# VFD_alpha_Sheet3.net
KiCad netlist of a schematic drawn in Altium Designer
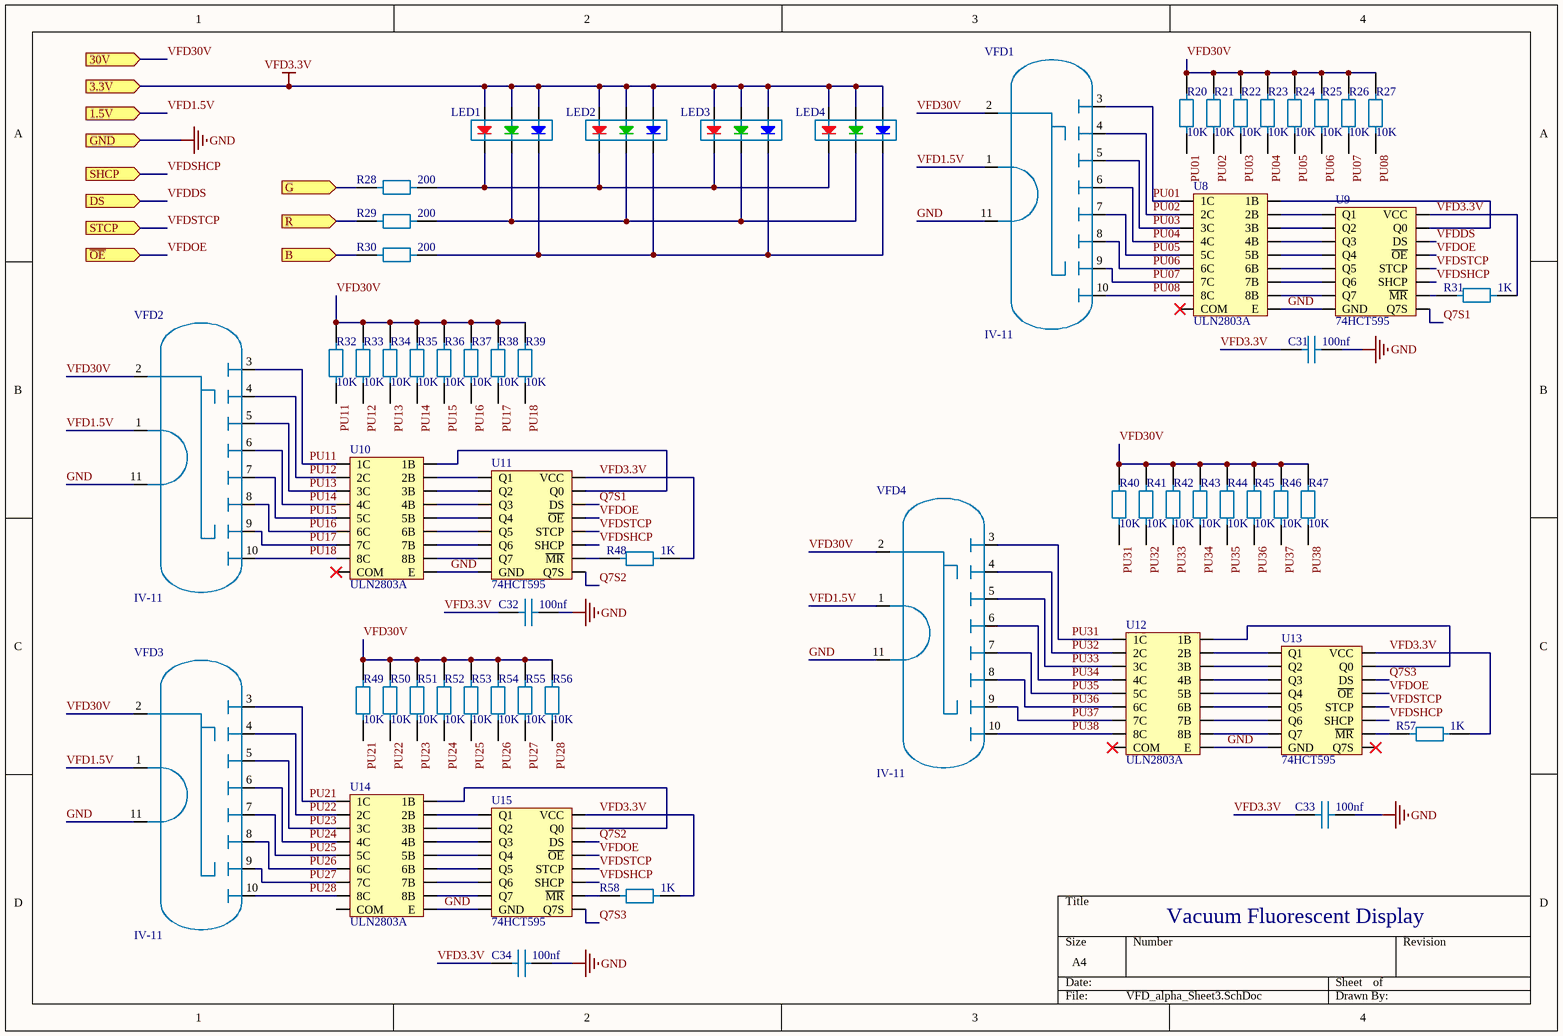
[diagram p0: VFD_alpha_Sheet3.SchDoc]

(export (version "E")
  (design (tool "Eeschema 10.0.6"))
  (components
    (comp (ref "C31")
      (value "100nf")
      (footprint "0603")
      (fields (field (name "Comment") "C"))
      (libsource (lib "ZZB_Lib") (part "C(0603)"))
    )
    (comp (ref "C32")
      (value "100nf")
      (footprint "0603")
      (fields (field (name "Comment") "C"))
      (libsource (lib "ZZB_Lib") (part "C(0603)"))
    )
    (comp (ref "C33")
      (value "100nf")
      (footprint "0603")
      (fields (field (name "Comment") "C"))
      (libsource (lib "ZZB_Lib") (part "C(0603)"))
    )
    (comp (ref "C34")
      (value "100nf")
      (footprint "0603")
      (fields (field (name "Comment") "C"))
      (libsource (lib "ZZB_Lib") (part "C(0603)"))
    )
    (comp (ref "LED1") (value "RGBLED") (footprint "RGBLED") (libsource (lib "ZZB_Lib") (part "RGBLED")))
    (comp (ref "LED2") (value "RGBLED") (footprint "RGBLED") (libsource (lib "ZZB_Lib") (part "RGBLED")))
    (comp (ref "LED3") (value "RGBLED") (footprint "RGBLED") (libsource (lib "ZZB_Lib") (part "RGBLED")))
    (comp (ref "LED4") (value "RGBLED") (footprint "RGBLED") (libsource (lib "ZZB_Lib") (part "RGBLED")))
    (comp (ref "R20")
      (value "10K")
      (footprint "R-1/4W")
      (fields (field (name "Comment") "R(1/4W)"))
      (libsource (lib "ZZB_Lib") (part "R(1/4W)"))
    )
    (comp (ref "R21")
      (value "10K")
      (footprint "R-1/4W")
      (fields (field (name "Comment") "R(1/4W)"))
      (libsource (lib "ZZB_Lib") (part "R(1/4W)"))
    )
    (comp (ref "R22")
      (value "10K")
      (footprint "R-1/4W")
      (fields (field (name "Comment") "R(1/4W)"))
      (libsource (lib "ZZB_Lib") (part "R(1/4W)"))
    )
    (comp (ref "R23")
      (value "10K")
      (footprint "R-1/4W")
      (fields (field (name "Comment") "R(1/4W)"))
      (libsource (lib "ZZB_Lib") (part "R(1/4W)"))
    )
    (comp (ref "R24")
      (value "10K")
      (footprint "R-1/4W")
      (fields (field (name "Comment") "R(1/4W)"))
      (libsource (lib "ZZB_Lib") (part "R(1/4W)"))
    )
    (comp (ref "R25")
      (value "10K")
      (footprint "R-1/4W")
      (fields (field (name "Comment") "R(1/4W)"))
      (libsource (lib "ZZB_Lib") (part "R(1/4W)"))
    )
    (comp (ref "R26")
      (value "10K")
      (footprint "R-1/4W")
      (fields (field (name "Comment") "R(1/4W)"))
      (libsource (lib "ZZB_Lib") (part "R(1/4W)"))
    )
    (comp (ref "R27")
      (value "10K")
      (footprint "R-1/4W")
      (fields (field (name "Comment") "R(1/4W)"))
      (libsource (lib "ZZB_Lib") (part "R(1/4W)"))
    )
    (comp (ref "R28")
      (value "200")
      (footprint "0603")
      (fields (field (name "Comment") "R"))
      (libsource (lib "ZZB_Lib") (part "R(0603)"))
    )
    (comp (ref "R29")
      (value "200")
      (footprint "0603")
      (fields (field (name "Comment") "R"))
      (libsource (lib "ZZB_Lib") (part "R(0603)"))
    )
    (comp (ref "R30")
      (value "200")
      (footprint "0603")
      (fields (field (name "Comment") "R"))
      (libsource (lib "ZZB_Lib") (part "R(0603)"))
    )
    (comp (ref "R31")
      (value "1K")
      (footprint "0603")
      (fields (field (name "Comment") "R"))
      (libsource (lib "ZZB_Lib") (part "R(0603)"))
    )
    (comp (ref "R32")
      (value "10K")
      (footprint "R-1/4W")
      (fields (field (name "Comment") "R(1/4W)"))
      (libsource (lib "ZZB_Lib") (part "R(1/4W)"))
    )
    (comp (ref "R33")
      (value "10K")
      (footprint "R-1/4W")
      (fields (field (name "Comment") "R(1/4W)"))
      (libsource (lib "ZZB_Lib") (part "R(1/4W)"))
    )
    (comp (ref "R34")
      (value "10K")
      (footprint "R-1/4W")
      (fields (field (name "Comment") "R(1/4W)"))
      (libsource (lib "ZZB_Lib") (part "R(1/4W)"))
    )
    (comp (ref "R35")
      (value "10K")
      (footprint "R-1/4W")
      (fields (field (name "Comment") "R(1/4W)"))
      (libsource (lib "ZZB_Lib") (part "R(1/4W)"))
    )
    (comp (ref "R36")
      (value "10K")
      (footprint "R-1/4W")
      (fields (field (name "Comment") "R(1/4W)"))
      (libsource (lib "ZZB_Lib") (part "R(1/4W)"))
    )
    (comp (ref "R37")
      (value "10K")
      (footprint "R-1/4W")
      (fields (field (name "Comment") "R(1/4W)"))
      (libsource (lib "ZZB_Lib") (part "R(1/4W)"))
    )
    (comp (ref "R38")
      (value "10K")
      (footprint "R-1/4W")
      (fields (field (name "Comment") "R(1/4W)"))
      (libsource (lib "ZZB_Lib") (part "R(1/4W)"))
    )
    (comp (ref "R39")
      (value "10K")
      (footprint "R-1/4W")
      (fields (field (name "Comment") "R(1/4W)"))
      (libsource (lib "ZZB_Lib") (part "R(1/4W)"))
    )
    (comp (ref "R40")
      (value "10K")
      (footprint "R-1/4W")
      (fields (field (name "Comment") "R(1/4W)"))
      (libsource (lib "ZZB_Lib") (part "R(1/4W)"))
    )
    (comp (ref "R41")
      (value "10K")
      (footprint "R-1/4W")
      (fields (field (name "Comment") "R(1/4W)"))
      (libsource (lib "ZZB_Lib") (part "R(1/4W)"))
    )
    (comp (ref "R42")
      (value "10K")
      (footprint "R-1/4W")
      (fields (field (name "Comment") "R(1/4W)"))
      (libsource (lib "ZZB_Lib") (part "R(1/4W)"))
    )
    (comp (ref "R43")
      (value "10K")
      (footprint "R-1/4W")
      (fields (field (name "Comment") "R(1/4W)"))
      (libsource (lib "ZZB_Lib") (part "R(1/4W)"))
    )
    (comp (ref "R44")
      (value "10K")
      (footprint "R-1/4W")
      (fields (field (name "Comment") "R(1/4W)"))
      (libsource (lib "ZZB_Lib") (part "R(1/4W)"))
    )
    (comp (ref "R45")
      (value "10K")
      (footprint "R-1/4W")
      (fields (field (name "Comment") "R(1/4W)"))
      (libsource (lib "ZZB_Lib") (part "R(1/4W)"))
    )
    (comp (ref "R46")
      (value "10K")
      (footprint "R-1/4W")
      (fields (field (name "Comment") "R(1/4W)"))
      (libsource (lib "ZZB_Lib") (part "R(1/4W)"))
    )
    (comp (ref "R47")
      (value "10K")
      (footprint "R-1/4W")
      (fields (field (name "Comment") "R(1/4W)"))
      (libsource (lib "ZZB_Lib") (part "R(1/4W)"))
    )
    (comp (ref "R48")
      (value "1K")
      (footprint "0603")
      (fields (field (name "Comment") "R"))
      (libsource (lib "ZZB_Lib") (part "R(0603)"))
    )
    (comp (ref "R49")
      (value "10K")
      (footprint "R-1/4W")
      (fields (field (name "Comment") "R(1/4W)"))
      (libsource (lib "ZZB_Lib") (part "R(1/4W)"))
    )
    (comp (ref "R50")
      (value "10K")
      (footprint "R-1/4W")
      (fields (field (name "Comment") "R(1/4W)"))
      (libsource (lib "ZZB_Lib") (part "R(1/4W)"))
    )
    (comp (ref "R51")
      (value "10K")
      (footprint "R-1/4W")
      (fields (field (name "Comment") "R(1/4W)"))
      (libsource (lib "ZZB_Lib") (part "R(1/4W)"))
    )
    (comp (ref "R52")
      (value "10K")
      (footprint "R-1/4W")
      (fields (field (name "Comment") "R(1/4W)"))
      (libsource (lib "ZZB_Lib") (part "R(1/4W)"))
    )
    (comp (ref "R53")
      (value "10K")
      (footprint "R-1/4W")
      (fields (field (name "Comment") "R(1/4W)"))
      (libsource (lib "ZZB_Lib") (part "R(1/4W)"))
    )
    (comp (ref "R54")
      (value "10K")
      (footprint "R-1/4W")
      (fields (field (name "Comment") "R(1/4W)"))
      (libsource (lib "ZZB_Lib") (part "R(1/4W)"))
    )
    (comp (ref "R55")
      (value "10K")
      (footprint "R-1/4W")
      (fields (field (name "Comment") "R(1/4W)"))
      (libsource (lib "ZZB_Lib") (part "R(1/4W)"))
    )
    (comp (ref "R56")
      (value "10K")
      (footprint "R-1/4W")
      (fields (field (name "Comment") "R(1/4W)"))
      (libsource (lib "ZZB_Lib") (part "R(1/4W)"))
    )
    (comp (ref "R57")
      (value "1K")
      (footprint "0603")
      (fields (field (name "Comment") "R"))
      (libsource (lib "ZZB_Lib") (part "R(0603)"))
    )
    (comp (ref "R58")
      (value "1K")
      (footprint "0603")
      (fields (field (name "Comment") "R"))
      (libsource (lib "ZZB_Lib") (part "R(0603)"))
    )
    (comp (ref "U8") (value "ULN2803A") (footprint "SOIC-18P") (libsource (lib "ZZB_Lib") (part "ULN2803A")))
    (comp (ref "U9") (value "74HCT595") (footprint "SOIC-16P") (libsource (lib "ZZB_Lib") (part "74HCT595")))
    (comp (ref "U10") (value "ULN2803A") (footprint "SOIC-18P") (libsource (lib "ZZB_Lib") (part "ULN2803A")))
    (comp (ref "U11") (value "74HCT595") (footprint "SOIC-16P") (libsource (lib "ZZB_Lib") (part "74HCT595")))
    (comp (ref "U12") (value "ULN2803A") (footprint "SOIC-18P") (libsource (lib "ZZB_Lib") (part "ULN2803A")))
    (comp (ref "U13") (value "74HCT595") (footprint "SOIC-16P") (libsource (lib "ZZB_Lib") (part "74HCT595")))
    (comp (ref "U14") (value "ULN2803A") (footprint "SOIC-18P") (libsource (lib "ZZB_Lib") (part "ULN2803A")))
    (comp (ref "U15") (value "74HCT595") (footprint "SOIC-16P") (libsource (lib "ZZB_Lib") (part "74HCT595")))
    (comp (ref "VFD1") (value "IV-11") (footprint "IV-11") (libsource (lib "ZZB_Lib") (part "IV-11")))
    (comp (ref "VFD2") (value "IV-11") (footprint "IV-11") (libsource (lib "ZZB_Lib") (part "IV-11")))
    (comp (ref "VFD3") (value "IV-11") (footprint "IV-11") (libsource (lib "ZZB_Lib") (part "IV-11")))
    (comp (ref "VFD4") (value "IV-11") (footprint "IV-11") (libsource (lib "ZZB_Lib") (part "IV-11")))
  )
  (nets
    (net (code "1") (name "/B") (class "Default")
      (node (ref "R30") (pin "2") (pinfunction "2_2") (pintype "passive"))
    )
    (net (code "2") (name "/G") (class "Default")
      (node (ref "R28") (pin "2") (pinfunction "2_2") (pintype "passive"))
    )
    (net (code "3") (name "/PU01") (class "Default")
      (node (ref "R20") (pin "1") (pinfunction "1_1") (pintype "passive"))
      (node (ref "U8") (pin "18") (pinfunction "1C_18") (pintype "passive"))
      (node (ref "VFD1") (pin "3") (pinfunction "3_3") (pintype "passive"))
    )
    (net (code "4") (name "/PU02") (class "Default")
      (node (ref "R21") (pin "1") (pinfunction "1_1") (pintype "passive"))
      (node (ref "U8") (pin "17") (pinfunction "2C_17") (pintype "passive"))
      (node (ref "VFD1") (pin "4") (pinfunction "4_4") (pintype "passive"))
    )
    (net (code "5") (name "/PU03") (class "Default")
      (node (ref "R22") (pin "1") (pinfunction "1_1") (pintype "passive"))
      (node (ref "U8") (pin "16") (pinfunction "3C_16") (pintype "passive"))
      (node (ref "VFD1") (pin "5") (pinfunction "5_5") (pintype "passive"))
    )
    (net (code "6") (name "/PU04") (class "Default")
      (node (ref "R23") (pin "1") (pinfunction "1_1") (pintype "passive"))
      (node (ref "U8") (pin "15") (pinfunction "4C_15") (pintype "passive"))
      (node (ref "VFD1") (pin "6") (pinfunction "6_6") (pintype "passive"))
    )
    (net (code "7") (name "/PU05") (class "Default")
      (node (ref "R24") (pin "1") (pinfunction "1_1") (pintype "passive"))
      (node (ref "U8") (pin "14") (pinfunction "5C_14") (pintype "passive"))
      (node (ref "VFD1") (pin "7") (pinfunction "7_7") (pintype "passive"))
    )
    (net (code "8") (name "/PU06") (class "Default")
      (node (ref "R25") (pin "1") (pinfunction "1_1") (pintype "passive"))
      (node (ref "U8") (pin "13") (pinfunction "6C_13") (pintype "passive"))
      (node (ref "VFD1") (pin "8") (pinfunction "8_8") (pintype "passive"))
    )
    (net (code "9") (name "/PU07") (class "Default")
      (node (ref "R26") (pin "1") (pinfunction "1_1") (pintype "passive"))
      (node (ref "U8") (pin "12") (pinfunction "7C_12") (pintype "passive"))
      (node (ref "VFD1") (pin "9") (pinfunction "9_9") (pintype "passive"))
    )
    (net (code "10") (name "/PU08") (class "Default")
      (node (ref "R27") (pin "1") (pinfunction "1_1") (pintype "passive"))
      (node (ref "U8") (pin "11") (pinfunction "8C_11") (pintype "passive"))
      (node (ref "VFD1") (pin "10") (pinfunction "10_10") (pintype "passive"))
    )
    (net (code "11") (name "/PU11") (class "Default")
      (node (ref "R32") (pin "1") (pinfunction "1_1") (pintype "passive"))
      (node (ref "U10") (pin "18") (pinfunction "1C_18") (pintype "passive"))
      (node (ref "VFD2") (pin "3") (pinfunction "3_3") (pintype "passive"))
    )
    (net (code "12") (name "/PU12") (class "Default")
      (node (ref "R33") (pin "1") (pinfunction "1_1") (pintype "passive"))
      (node (ref "U10") (pin "17") (pinfunction "2C_17") (pintype "passive"))
      (node (ref "VFD2") (pin "4") (pinfunction "4_4") (pintype "passive"))
    )
    (net (code "13") (name "/PU13") (class "Default")
      (node (ref "R34") (pin "1") (pinfunction "1_1") (pintype "passive"))
      (node (ref "U10") (pin "16") (pinfunction "3C_16") (pintype "passive"))
      (node (ref "VFD2") (pin "5") (pinfunction "5_5") (pintype "passive"))
    )
    (net (code "14") (name "/PU14") (class "Default")
      (node (ref "R35") (pin "1") (pinfunction "1_1") (pintype "passive"))
      (node (ref "U10") (pin "15") (pinfunction "4C_15") (pintype "passive"))
      (node (ref "VFD2") (pin "6") (pinfunction "6_6") (pintype "passive"))
    )
    (net (code "15") (name "/PU15") (class "Default")
      (node (ref "R36") (pin "1") (pinfunction "1_1") (pintype "passive"))
      (node (ref "U10") (pin "14") (pinfunction "5C_14") (pintype "passive"))
      (node (ref "VFD2") (pin "7") (pinfunction "7_7") (pintype "passive"))
    )
    (net (code "16") (name "/PU16") (class "Default")
      (node (ref "R37") (pin "1") (pinfunction "1_1") (pintype "passive"))
      (node (ref "U10") (pin "13") (pinfunction "6C_13") (pintype "passive"))
      (node (ref "VFD2") (pin "8") (pinfunction "8_8") (pintype "passive"))
    )
    (net (code "17") (name "/PU17") (class "Default")
      (node (ref "R38") (pin "1") (pinfunction "1_1") (pintype "passive"))
      (node (ref "U10") (pin "12") (pinfunction "7C_12") (pintype "passive"))
      (node (ref "VFD2") (pin "9") (pinfunction "9_9") (pintype "passive"))
    )
    (net (code "18") (name "/PU18") (class "Default")
      (node (ref "R39") (pin "1") (pinfunction "1_1") (pintype "passive"))
      (node (ref "U10") (pin "11") (pinfunction "8C_11") (pintype "passive"))
      (node (ref "VFD2") (pin "10") (pinfunction "10_10") (pintype "passive"))
    )
    (net (code "19") (name "/PU21") (class "Default")
      (node (ref "R49") (pin "1") (pinfunction "1_1") (pintype "passive"))
      (node (ref "U14") (pin "18") (pinfunction "1C_18") (pintype "passive"))
      (node (ref "VFD3") (pin "3") (pinfunction "3_3") (pintype "passive"))
    )
    (net (code "20") (name "/PU22") (class "Default")
      (node (ref "R50") (pin "1") (pinfunction "1_1") (pintype "passive"))
      (node (ref "U14") (pin "17") (pinfunction "2C_17") (pintype "passive"))
      (node (ref "VFD3") (pin "4") (pinfunction "4_4") (pintype "passive"))
    )
    (net (code "21") (name "/PU23") (class "Default")
      (node (ref "R51") (pin "1") (pinfunction "1_1") (pintype "passive"))
      (node (ref "U14") (pin "16") (pinfunction "3C_16") (pintype "passive"))
      (node (ref "VFD3") (pin "5") (pinfunction "5_5") (pintype "passive"))
    )
    (net (code "22") (name "/PU24") (class "Default")
      (node (ref "R52") (pin "1") (pinfunction "1_1") (pintype "passive"))
      (node (ref "U14") (pin "15") (pinfunction "4C_15") (pintype "passive"))
      (node (ref "VFD3") (pin "6") (pinfunction "6_6") (pintype "passive"))
    )
    (net (code "23") (name "/PU25") (class "Default")
      (node (ref "R53") (pin "1") (pinfunction "1_1") (pintype "passive"))
      (node (ref "U14") (pin "14") (pinfunction "5C_14") (pintype "passive"))
      (node (ref "VFD3") (pin "7") (pinfunction "7_7") (pintype "passive"))
    )
    (net (code "24") (name "/PU26") (class "Default")
      (node (ref "R54") (pin "1") (pinfunction "1_1") (pintype "passive"))
      (node (ref "U14") (pin "13") (pinfunction "6C_13") (pintype "passive"))
      (node (ref "VFD3") (pin "8") (pinfunction "8_8") (pintype "passive"))
    )
    (net (code "25") (name "/PU27") (class "Default")
      (node (ref "R55") (pin "1") (pinfunction "1_1") (pintype "passive"))
      (node (ref "U14") (pin "12") (pinfunction "7C_12") (pintype "passive"))
      (node (ref "VFD3") (pin "9") (pinfunction "9_9") (pintype "passive"))
    )
    (net (code "26") (name "/PU28") (class "Default")
      (node (ref "R56") (pin "1") (pinfunction "1_1") (pintype "passive"))
      (node (ref "U14") (pin "11") (pinfunction "8C_11") (pintype "passive"))
      (node (ref "VFD3") (pin "10") (pinfunction "10_10") (pintype "passive"))
    )
    (net (code "27") (name "/PU31") (class "Default")
      (node (ref "R40") (pin "1") (pinfunction "1_1") (pintype "passive"))
      (node (ref "U12") (pin "18") (pinfunction "1C_18") (pintype "passive"))
      (node (ref "VFD4") (pin "3") (pinfunction "3_3") (pintype "passive"))
    )
    (net (code "28") (name "/PU32") (class "Default")
      (node (ref "R41") (pin "1") (pinfunction "1_1") (pintype "passive"))
      (node (ref "U12") (pin "17") (pinfunction "2C_17") (pintype "passive"))
      (node (ref "VFD4") (pin "4") (pinfunction "4_4") (pintype "passive"))
    )
    (net (code "29") (name "/PU33") (class "Default")
      (node (ref "R42") (pin "1") (pinfunction "1_1") (pintype "passive"))
      (node (ref "U12") (pin "16") (pinfunction "3C_16") (pintype "passive"))
      (node (ref "VFD4") (pin "5") (pinfunction "5_5") (pintype "passive"))
    )
    (net (code "30") (name "/PU34") (class "Default")
      (node (ref "R43") (pin "1") (pinfunction "1_1") (pintype "passive"))
      (node (ref "U12") (pin "15") (pinfunction "4C_15") (pintype "passive"))
      (node (ref "VFD4") (pin "6") (pinfunction "6_6") (pintype "passive"))
    )
    (net (code "31") (name "/PU35") (class "Default")
      (node (ref "R44") (pin "1") (pinfunction "1_1") (pintype "passive"))
      (node (ref "U12") (pin "14") (pinfunction "5C_14") (pintype "passive"))
      (node (ref "VFD4") (pin "7") (pinfunction "7_7") (pintype "passive"))
    )
    (net (code "32") (name "/PU36") (class "Default")
      (node (ref "R45") (pin "1") (pinfunction "1_1") (pintype "passive"))
      (node (ref "U12") (pin "13") (pinfunction "6C_13") (pintype "passive"))
      (node (ref "VFD4") (pin "8") (pinfunction "8_8") (pintype "passive"))
    )
    (net (code "33") (name "/PU37") (class "Default")
      (node (ref "R46") (pin "1") (pinfunction "1_1") (pintype "passive"))
      (node (ref "U12") (pin "12") (pinfunction "7C_12") (pintype "passive"))
      (node (ref "VFD4") (pin "9") (pinfunction "9_9") (pintype "passive"))
    )
    (net (code "34") (name "/PU38") (class "Default")
      (node (ref "R47") (pin "1") (pinfunction "1_1") (pintype "passive"))
      (node (ref "U12") (pin "11") (pinfunction "8C_11") (pintype "passive"))
      (node (ref "VFD4") (pin "10") (pinfunction "10_10") (pintype "passive"))
    )
    (net (code "35") (name "/Q7S1") (class "Default")
      (node (ref "U11") (pin "14") (pinfunction "DS_14") (pintype "passive"))
      (node (ref "U9") (pin "9") (pinfunction "Q7S_9") (pintype "passive"))
    )
    (net (code "36") (name "/Q7S2") (class "Default")
      (node (ref "U11") (pin "9") (pinfunction "Q7S_9") (pintype "passive"))
      (node (ref "U15") (pin "14") (pinfunction "DS_14") (pintype "passive"))
    )
    (net (code "37") (name "/Q7S3") (class "Default")
      (node (ref "U13") (pin "14") (pinfunction "DS_14") (pintype "passive"))
      (node (ref "U15") (pin "9") (pinfunction "Q7S_9") (pintype "passive"))
    )
    (net (code "38") (name "/R") (class "Default")
      (node (ref "R29") (pin "2") (pinfunction "2_2") (pintype "passive"))
    )
    (net (code "39") (name "/VFD1.5V") (class "Default")
      (node (ref "VFD1") (pin "1") (pinfunction "1_1") (pintype "passive"))
      (node (ref "VFD2") (pin "1") (pinfunction "1_1") (pintype "passive"))
      (node (ref "VFD3") (pin "1") (pinfunction "1_1") (pintype "passive"))
      (node (ref "VFD4") (pin "1") (pinfunction "1_1") (pintype "passive"))
    )
    (net (code "40") (name "/VFD30V") (class "Default")
      (node (ref "R20") (pin "2") (pinfunction "2_2") (pintype "passive"))
      (node (ref "R21") (pin "2") (pinfunction "2_2") (pintype "passive"))
      (node (ref "R22") (pin "2") (pinfunction "2_2") (pintype "passive"))
      (node (ref "R23") (pin "2") (pinfunction "2_2") (pintype "passive"))
      (node (ref "R24") (pin "2") (pinfunction "2_2") (pintype "passive"))
      (node (ref "R25") (pin "2") (pinfunction "2_2") (pintype "passive"))
      (node (ref "R26") (pin "2") (pinfunction "2_2") (pintype "passive"))
      (node (ref "R27") (pin "2") (pinfunction "2_2") (pintype "passive"))
      (node (ref "R32") (pin "2") (pinfunction "2_2") (pintype "passive"))
      (node (ref "R33") (pin "2") (pinfunction "2_2") (pintype "passive"))
      (node (ref "R34") (pin "2") (pinfunction "2_2") (pintype "passive"))
      (node (ref "R35") (pin "2") (pinfunction "2_2") (pintype "passive"))
      (node (ref "R36") (pin "2") (pinfunction "2_2") (pintype "passive"))
      (node (ref "R37") (pin "2") (pinfunction "2_2") (pintype "passive"))
      (node (ref "R38") (pin "2") (pinfunction "2_2") (pintype "passive"))
      (node (ref "R39") (pin "2") (pinfunction "2_2") (pintype "passive"))
      (node (ref "R40") (pin "2") (pinfunction "2_2") (pintype "passive"))
      (node (ref "R41") (pin "2") (pinfunction "2_2") (pintype "passive"))
      (node (ref "R42") (pin "2") (pinfunction "2_2") (pintype "passive"))
      (node (ref "R43") (pin "2") (pinfunction "2_2") (pintype "passive"))
      (node (ref "R44") (pin "2") (pinfunction "2_2") (pintype "passive"))
      (node (ref "R45") (pin "2") (pinfunction "2_2") (pintype "passive"))
      (node (ref "R46") (pin "2") (pinfunction "2_2") (pintype "passive"))
      (node (ref "R47") (pin "2") (pinfunction "2_2") (pintype "passive"))
      (node (ref "R49") (pin "2") (pinfunction "2_2") (pintype "passive"))
      (node (ref "R50") (pin "2") (pinfunction "2_2") (pintype "passive"))
      (node (ref "R51") (pin "2") (pinfunction "2_2") (pintype "passive"))
      (node (ref "R52") (pin "2") (pinfunction "2_2") (pintype "passive"))
      (node (ref "R53") (pin "2") (pinfunction "2_2") (pintype "passive"))
      (node (ref "R54") (pin "2") (pinfunction "2_2") (pintype "passive"))
      (node (ref "R55") (pin "2") (pinfunction "2_2") (pintype "passive"))
      (node (ref "R56") (pin "2") (pinfunction "2_2") (pintype "passive"))
      (node (ref "VFD1") (pin "2") (pinfunction "2_2") (pintype "passive"))
      (node (ref "VFD2") (pin "2") (pinfunction "2_2") (pintype "passive"))
      (node (ref "VFD3") (pin "2") (pinfunction "2_2") (pintype "passive"))
      (node (ref "VFD4") (pin "2") (pinfunction "2_2") (pintype "passive"))
    )
    (net (code "41") (name "/VFDDS") (class "Default")
      (node (ref "U9") (pin "14") (pinfunction "DS_14") (pintype "passive"))
    )
    (net (code "42") (name "/VFDOE") (class "Default")
      (node (ref "U11") (pin "13") (pinfunction "~{OE}_13") (pintype "passive"))
      (node (ref "U13") (pin "13") (pinfunction "~{OE}_13") (pintype "passive"))
      (node (ref "U15") (pin "13") (pinfunction "~{OE}_13") (pintype "passive"))
      (node (ref "U9") (pin "13") (pinfunction "~{OE}_13") (pintype "passive"))
    )
    (net (code "43") (name "/VFDSHCP") (class "Default")
      (node (ref "U11") (pin "11") (pinfunction "SHCP_11") (pintype "passive"))
      (node (ref "U13") (pin "11") (pinfunction "SHCP_11") (pintype "passive"))
      (node (ref "U15") (pin "11") (pinfunction "SHCP_11") (pintype "passive"))
      (node (ref "U9") (pin "11") (pinfunction "SHCP_11") (pintype "passive"))
    )
    (net (code "44") (name "/VFDSTCP") (class "Default")
      (node (ref "U11") (pin "12") (pinfunction "STCP_12") (pintype "passive"))
      (node (ref "U13") (pin "12") (pinfunction "STCP_12") (pintype "passive"))
      (node (ref "U15") (pin "12") (pinfunction "STCP_12") (pintype "passive"))
      (node (ref "U9") (pin "12") (pinfunction "STCP_12") (pintype "passive"))
    )
    (net (code "45") (name "GND") (class "Default")
      (node (ref "C31") (pin "1") (pinfunction "1_1") (pintype "passive"))
      (node (ref "C32") (pin "2") (pinfunction "2_2") (pintype "passive"))
      (node (ref "C33") (pin "2") (pinfunction "2_2") (pintype "passive"))
      (node (ref "C34") (pin "2") (pinfunction "2_2") (pintype "passive"))
      (node (ref "U10") (pin "9") (pinfunction "E_9") (pintype "passive"))
      (node (ref "U11") (pin "8") (pinfunction "GND_8") (pintype "passive"))
      (node (ref "U12") (pin "9") (pinfunction "E_9") (pintype "passive"))
      (node (ref "U13") (pin "8") (pinfunction "GND_8") (pintype "passive"))
      (node (ref "U14") (pin "9") (pinfunction "E_9") (pintype "passive"))
      (node (ref "U15") (pin "8") (pinfunction "GND_8") (pintype "passive"))
      (node (ref "U8") (pin "9") (pinfunction "E_9") (pintype "passive"))
      (node (ref "U9") (pin "8") (pinfunction "GND_8") (pintype "passive"))
      (node (ref "VFD1") (pin "11") (pinfunction "11_11") (pintype "passive"))
      (node (ref "VFD2") (pin "11") (pinfunction "11_11") (pintype "passive"))
      (node (ref "VFD3") (pin "11") (pinfunction "11_11") (pintype "passive"))
      (node (ref "VFD4") (pin "11") (pinfunction "11_11") (pintype "passive"))
    )
    (net (code "46") (name "Net-(LED1-Pad4)") (class "Default")
      (node (ref "LED1") (pin "4") (pinfunction "4_4") (pintype "passive"))
      (node (ref "LED2") (pin "4") (pinfunction "4_4") (pintype "passive"))
      (node (ref "LED3") (pin "4") (pinfunction "4_4") (pintype "passive"))
      (node (ref "LED4") (pin "4") (pinfunction "4_4") (pintype "passive"))
      (node (ref "R30") (pin "1") (pinfunction "1_1") (pintype "passive"))
    )
    (net (code "47") (name "Net-(LED1-Pad5)") (class "Default")
      (node (ref "LED1") (pin "5") (pinfunction "5_5") (pintype "passive"))
      (node (ref "LED2") (pin "5") (pinfunction "5_5") (pintype "passive"))
      (node (ref "LED3") (pin "5") (pinfunction "5_5") (pintype "passive"))
      (node (ref "LED4") (pin "5") (pinfunction "5_5") (pintype "passive"))
      (node (ref "R29") (pin "1") (pinfunction "1_1") (pintype "passive"))
    )
    (net (code "48") (name "Net-(LED1-Pad6)") (class "Default")
      (node (ref "LED1") (pin "6") (pinfunction "6_6") (pintype "passive"))
      (node (ref "LED2") (pin "6") (pinfunction "6_6") (pintype "passive"))
      (node (ref "LED3") (pin "6") (pinfunction "6_6") (pintype "passive"))
      (node (ref "LED4") (pin "6") (pinfunction "6_6") (pintype "passive"))
      (node (ref "R28") (pin "1") (pinfunction "1_1") (pintype "passive"))
    )
    (net (code "49") (name "Net-(U8-1B)") (class "Default")
      (node (ref "U8") (pin "1") (pinfunction "1B_1") (pintype "passive"))
      (node (ref "U9") (pin "15") (pinfunction "Q0_15") (pintype "passive"))
    )
    (net (code "50") (name "Net-(U8-2B)") (class "Default")
      (node (ref "U8") (pin "2") (pinfunction "2B_2") (pintype "passive"))
      (node (ref "U9") (pin "1") (pinfunction "Q1_1") (pintype "passive"))
    )
    (net (code "51") (name "Net-(U8-3B)") (class "Default")
      (node (ref "U8") (pin "3") (pinfunction "3B_3") (pintype "passive"))
      (node (ref "U9") (pin "2") (pinfunction "Q2_2") (pintype "passive"))
    )
    (net (code "52") (name "Net-(U8-4B)") (class "Default")
      (node (ref "U8") (pin "4") (pinfunction "4B_4") (pintype "passive"))
      (node (ref "U9") (pin "3") (pinfunction "Q3_3") (pintype "passive"))
    )
    (net (code "53") (name "Net-(U8-5B)") (class "Default")
      (node (ref "U8") (pin "5") (pinfunction "5B_5") (pintype "passive"))
      (node (ref "U9") (pin "4") (pinfunction "Q4_4") (pintype "passive"))
    )
    (net (code "54") (name "Net-(U8-6B)") (class "Default")
      (node (ref "U8") (pin "6") (pinfunction "6B_6") (pintype "passive"))
      (node (ref "U9") (pin "5") (pinfunction "Q5_5") (pintype "passive"))
    )
    (net (code "55") (name "Net-(U8-7B)") (class "Default")
      (node (ref "U8") (pin "7") (pinfunction "7B_7") (pintype "passive"))
      (node (ref "U9") (pin "6") (pinfunction "Q6_6") (pintype "passive"))
    )
    (net (code "56") (name "Net-(U8-8B)") (class "Default")
      (node (ref "U8") (pin "8") (pinfunction "8B_8") (pintype "passive"))
      (node (ref "U9") (pin "7") (pinfunction "Q7_7") (pintype "passive"))
    )
    (net (code "57") (name "Net-(U9-~{MR})") (class "Default")
      (node (ref "R31") (pin "1") (pinfunction "1_1") (pintype "passive"))
      (node (ref "U9") (pin "10") (pinfunction "~{MR}_10") (pintype "passive"))
    )
    (net (code "58") (name "Net-(U10-1B)") (class "Default")
      (node (ref "U10") (pin "1") (pinfunction "1B_1") (pintype "passive"))
      (node (ref "U11") (pin "15") (pinfunction "Q0_15") (pintype "passive"))
    )
    (net (code "59") (name "Net-(U10-2B)") (class "Default")
      (node (ref "U10") (pin "2") (pinfunction "2B_2") (pintype "passive"))
      (node (ref "U11") (pin "1") (pinfunction "Q1_1") (pintype "passive"))
    )
    (net (code "60") (name "Net-(U10-3B)") (class "Default")
      (node (ref "U10") (pin "3") (pinfunction "3B_3") (pintype "passive"))
      (node (ref "U11") (pin "2") (pinfunction "Q2_2") (pintype "passive"))
    )
    (net (code "61") (name "Net-(U10-4B)") (class "Default")
      (node (ref "U10") (pin "4") (pinfunction "4B_4") (pintype "passive"))
      (node (ref "U11") (pin "3") (pinfunction "Q3_3") (pintype "passive"))
    )
    (net (code "62") (name "Net-(U10-5B)") (class "Default")
      (node (ref "U10") (pin "5") (pinfunction "5B_5") (pintype "passive"))
      (node (ref "U11") (pin "4") (pinfunction "Q4_4") (pintype "passive"))
    )
    (net (code "63") (name "Net-(U10-6B)") (class "Default")
      (node (ref "U10") (pin "6") (pinfunction "6B_6") (pintype "passive"))
      (node (ref "U11") (pin "5") (pinfunction "Q5_5") (pintype "passive"))
    )
    (net (code "64") (name "Net-(U10-7B)") (class "Default")
      (node (ref "U10") (pin "7") (pinfunction "7B_7") (pintype "passive"))
      (node (ref "U11") (pin "6") (pinfunction "Q6_6") (pintype "passive"))
    )
    (net (code "65") (name "Net-(U10-8B)") (class "Default")
      (node (ref "U10") (pin "8") (pinfunction "8B_8") (pintype "passive"))
      (node (ref "U11") (pin "7") (pinfunction "Q7_7") (pintype "passive"))
    )
    (net (code "66") (name "Net-(U11-~{MR})") (class "Default")
      (node (ref "R48") (pin "1") (pinfunction "1_1") (pintype "passive"))
      (node (ref "U11") (pin "10") (pinfunction "~{MR}_10") (pintype "passive"))
    )
    (net (code "67") (name "Net-(U12-1B)") (class "Default")
      (node (ref "U12") (pin "1") (pinfunction "1B_1") (pintype "passive"))
      (node (ref "U13") (pin "15") (pinfunction "Q0_15") (pintype "passive"))
    )
    (net (code "68") (name "Net-(U12-2B)") (class "Default")
      (node (ref "U12") (pin "2") (pinfunction "2B_2") (pintype "passive"))
      (node (ref "U13") (pin "1") (pinfunction "Q1_1") (pintype "passive"))
    )
    (net (code "69") (name "Net-(U12-3B)") (class "Default")
      (node (ref "U12") (pin "3") (pinfunction "3B_3") (pintype "passive"))
      (node (ref "U13") (pin "2") (pinfunction "Q2_2") (pintype "passive"))
    )
    (net (code "70") (name "Net-(U12-4B)") (class "Default")
      (node (ref "U12") (pin "4") (pinfunction "4B_4") (pintype "passive"))
      (node (ref "U13") (pin "3") (pinfunction "Q3_3") (pintype "passive"))
    )
    (net (code "71") (name "Net-(U12-5B)") (class "Default")
      (node (ref "U12") (pin "5") (pinfunction "5B_5") (pintype "passive"))
      (node (ref "U13") (pin "4") (pinfunction "Q4_4") (pintype "passive"))
    )
    (net (code "72") (name "Net-(U12-6B)") (class "Default")
      (node (ref "U12") (pin "6") (pinfunction "6B_6") (pintype "passive"))
      (node (ref "U13") (pin "5") (pinfunction "Q5_5") (pintype "passive"))
    )
    (net (code "73") (name "Net-(U12-7B)") (class "Default")
      (node (ref "U12") (pin "7") (pinfunction "7B_7") (pintype "passive"))
      (node (ref "U13") (pin "6") (pinfunction "Q6_6") (pintype "passive"))
    )
    (net (code "74") (name "Net-(U12-8B)") (class "Default")
      (node (ref "U12") (pin "8") (pinfunction "8B_8") (pintype "passive"))
      (node (ref "U13") (pin "7") (pinfunction "Q7_7") (pintype "passive"))
    )
    (net (code "75") (name "Net-(U13-~{MR})") (class "Default")
      (node (ref "R57") (pin "1") (pinfunction "1_1") (pintype "passive"))
      (node (ref "U13") (pin "10") (pinfunction "~{MR}_10") (pintype "passive"))
    )
    (net (code "76") (name "Net-(U14-1B)") (class "Default")
      (node (ref "U14") (pin "1") (pinfunction "1B_1") (pintype "passive"))
      (node (ref "U15") (pin "15") (pinfunction "Q0_15") (pintype "passive"))
    )
    (net (code "77") (name "Net-(U14-2B)") (class "Default")
      (node (ref "U14") (pin "2") (pinfunction "2B_2") (pintype "passive"))
      (node (ref "U15") (pin "1") (pinfunction "Q1_1") (pintype "passive"))
    )
    (net (code "78") (name "Net-(U14-3B)") (class "Default")
      (node (ref "U14") (pin "3") (pinfunction "3B_3") (pintype "passive"))
      (node (ref "U15") (pin "2") (pinfunction "Q2_2") (pintype "passive"))
    )
    (net (code "79") (name "Net-(U14-4B)") (class "Default")
      (node (ref "U14") (pin "4") (pinfunction "4B_4") (pintype "passive"))
      (node (ref "U15") (pin "3") (pinfunction "Q3_3") (pintype "passive"))
    )
    (net (code "80") (name "Net-(U14-5B)") (class "Default")
      (node (ref "U14") (pin "5") (pinfunction "5B_5") (pintype "passive"))
      (node (ref "U15") (pin "4") (pinfunction "Q4_4") (pintype "passive"))
    )
    (net (code "81") (name "Net-(U14-6B)") (class "Default")
      (node (ref "U14") (pin "6") (pinfunction "6B_6") (pintype "passive"))
      (node (ref "U15") (pin "5") (pinfunction "Q5_5") (pintype "passive"))
    )
    (net (code "82") (name "Net-(U14-7B)") (class "Default")
      (node (ref "U14") (pin "7") (pinfunction "7B_7") (pintype "passive"))
      (node (ref "U15") (pin "6") (pinfunction "Q6_6") (pintype "passive"))
    )
    (net (code "83") (name "Net-(U14-8B)") (class "Default")
      (node (ref "U14") (pin "8") (pinfunction "8B_8") (pintype "passive"))
      (node (ref "U15") (pin "7") (pinfunction "Q7_7") (pintype "passive"))
    )
    (net (code "84") (name "Net-(U15-~{MR})") (class "Default")
      (node (ref "R58") (pin "1") (pinfunction "1_1") (pintype "passive"))
      (node (ref "U15") (pin "10") (pinfunction "~{MR}_10") (pintype "passive"))
    )
    (net (code "85") (name "VFD3.3V") (class "Default")
      (node (ref "C31") (pin "2") (pinfunction "2_2") (pintype "passive"))
      (node (ref "C32") (pin "1") (pinfunction "1_1") (pintype "passive"))
      (node (ref "C33") (pin "1") (pinfunction "1_1") (pintype "passive"))
      (node (ref "C34") (pin "1") (pinfunction "1_1") (pintype "passive"))
      (node (ref "LED1") (pin "1") (pinfunction "1_1") (pintype "passive"))
      (node (ref "LED1") (pin "2") (pinfunction "2_2") (pintype "passive"))
      (node (ref "LED1") (pin "3") (pinfunction "3_3") (pintype "passive"))
      (node (ref "LED2") (pin "1") (pinfunction "1_1") (pintype "passive"))
      (node (ref "LED2") (pin "2") (pinfunction "2_2") (pintype "passive"))
      (node (ref "LED2") (pin "3") (pinfunction "3_3") (pintype "passive"))
      (node (ref "LED3") (pin "1") (pinfunction "1_1") (pintype "passive"))
      (node (ref "LED3") (pin "2") (pinfunction "2_2") (pintype "passive"))
      (node (ref "LED3") (pin "3") (pinfunction "3_3") (pintype "passive"))
      (node (ref "LED4") (pin "1") (pinfunction "1_1") (pintype "passive"))
      (node (ref "LED4") (pin "2") (pinfunction "2_2") (pintype "passive"))
      (node (ref "LED4") (pin "3") (pinfunction "3_3") (pintype "passive"))
      (node (ref "R31") (pin "2") (pinfunction "2_2") (pintype "passive"))
      (node (ref "R48") (pin "2") (pinfunction "2_2") (pintype "passive"))
      (node (ref "R57") (pin "2") (pinfunction "2_2") (pintype "passive"))
      (node (ref "R58") (pin "2") (pinfunction "2_2") (pintype "passive"))
      (node (ref "U11") (pin "16") (pinfunction "VCC_16") (pintype "passive"))
      (node (ref "U13") (pin "16") (pinfunction "VCC_16") (pintype "passive"))
      (node (ref "U15") (pin "16") (pinfunction "VCC_16") (pintype "passive"))
      (node (ref "U9") (pin "16") (pinfunction "VCC_16") (pintype "passive"))
    )
    (net (code "86") (name "unconnected-(U8-COM-Pad10)") (class "Default")
      (node (ref "U8") (pin "10") (pinfunction "COM_10") (pintype "passive+no_connect"))
    )
    (net (code "87") (name "unconnected-(U10-COM-Pad10)") (class "Default")
      (node (ref "U10") (pin "10") (pinfunction "COM_10") (pintype "passive+no_connect"))
    )
    (net (code "88") (name "unconnected-(U12-COM-Pad10)") (class "Default")
      (node (ref "U12") (pin "10") (pinfunction "COM_10") (pintype "passive+no_connect"))
    )
    (net (code "89") (name "unconnected-(U13-Q7S-Pad9)") (class "Default")
      (node (ref "U13") (pin "9") (pinfunction "Q7S_9") (pintype "passive+no_connect"))
    )
    (net (code "90") (name "unconnected-(U14-COM-Pad10)") (class "Default")
      (node (ref "U14") (pin "10") (pinfunction "COM_10") (pintype "passive"))
    )
  )
)
